# Motor.net
KiCad netlist of a schematic drawn in Altium Designer
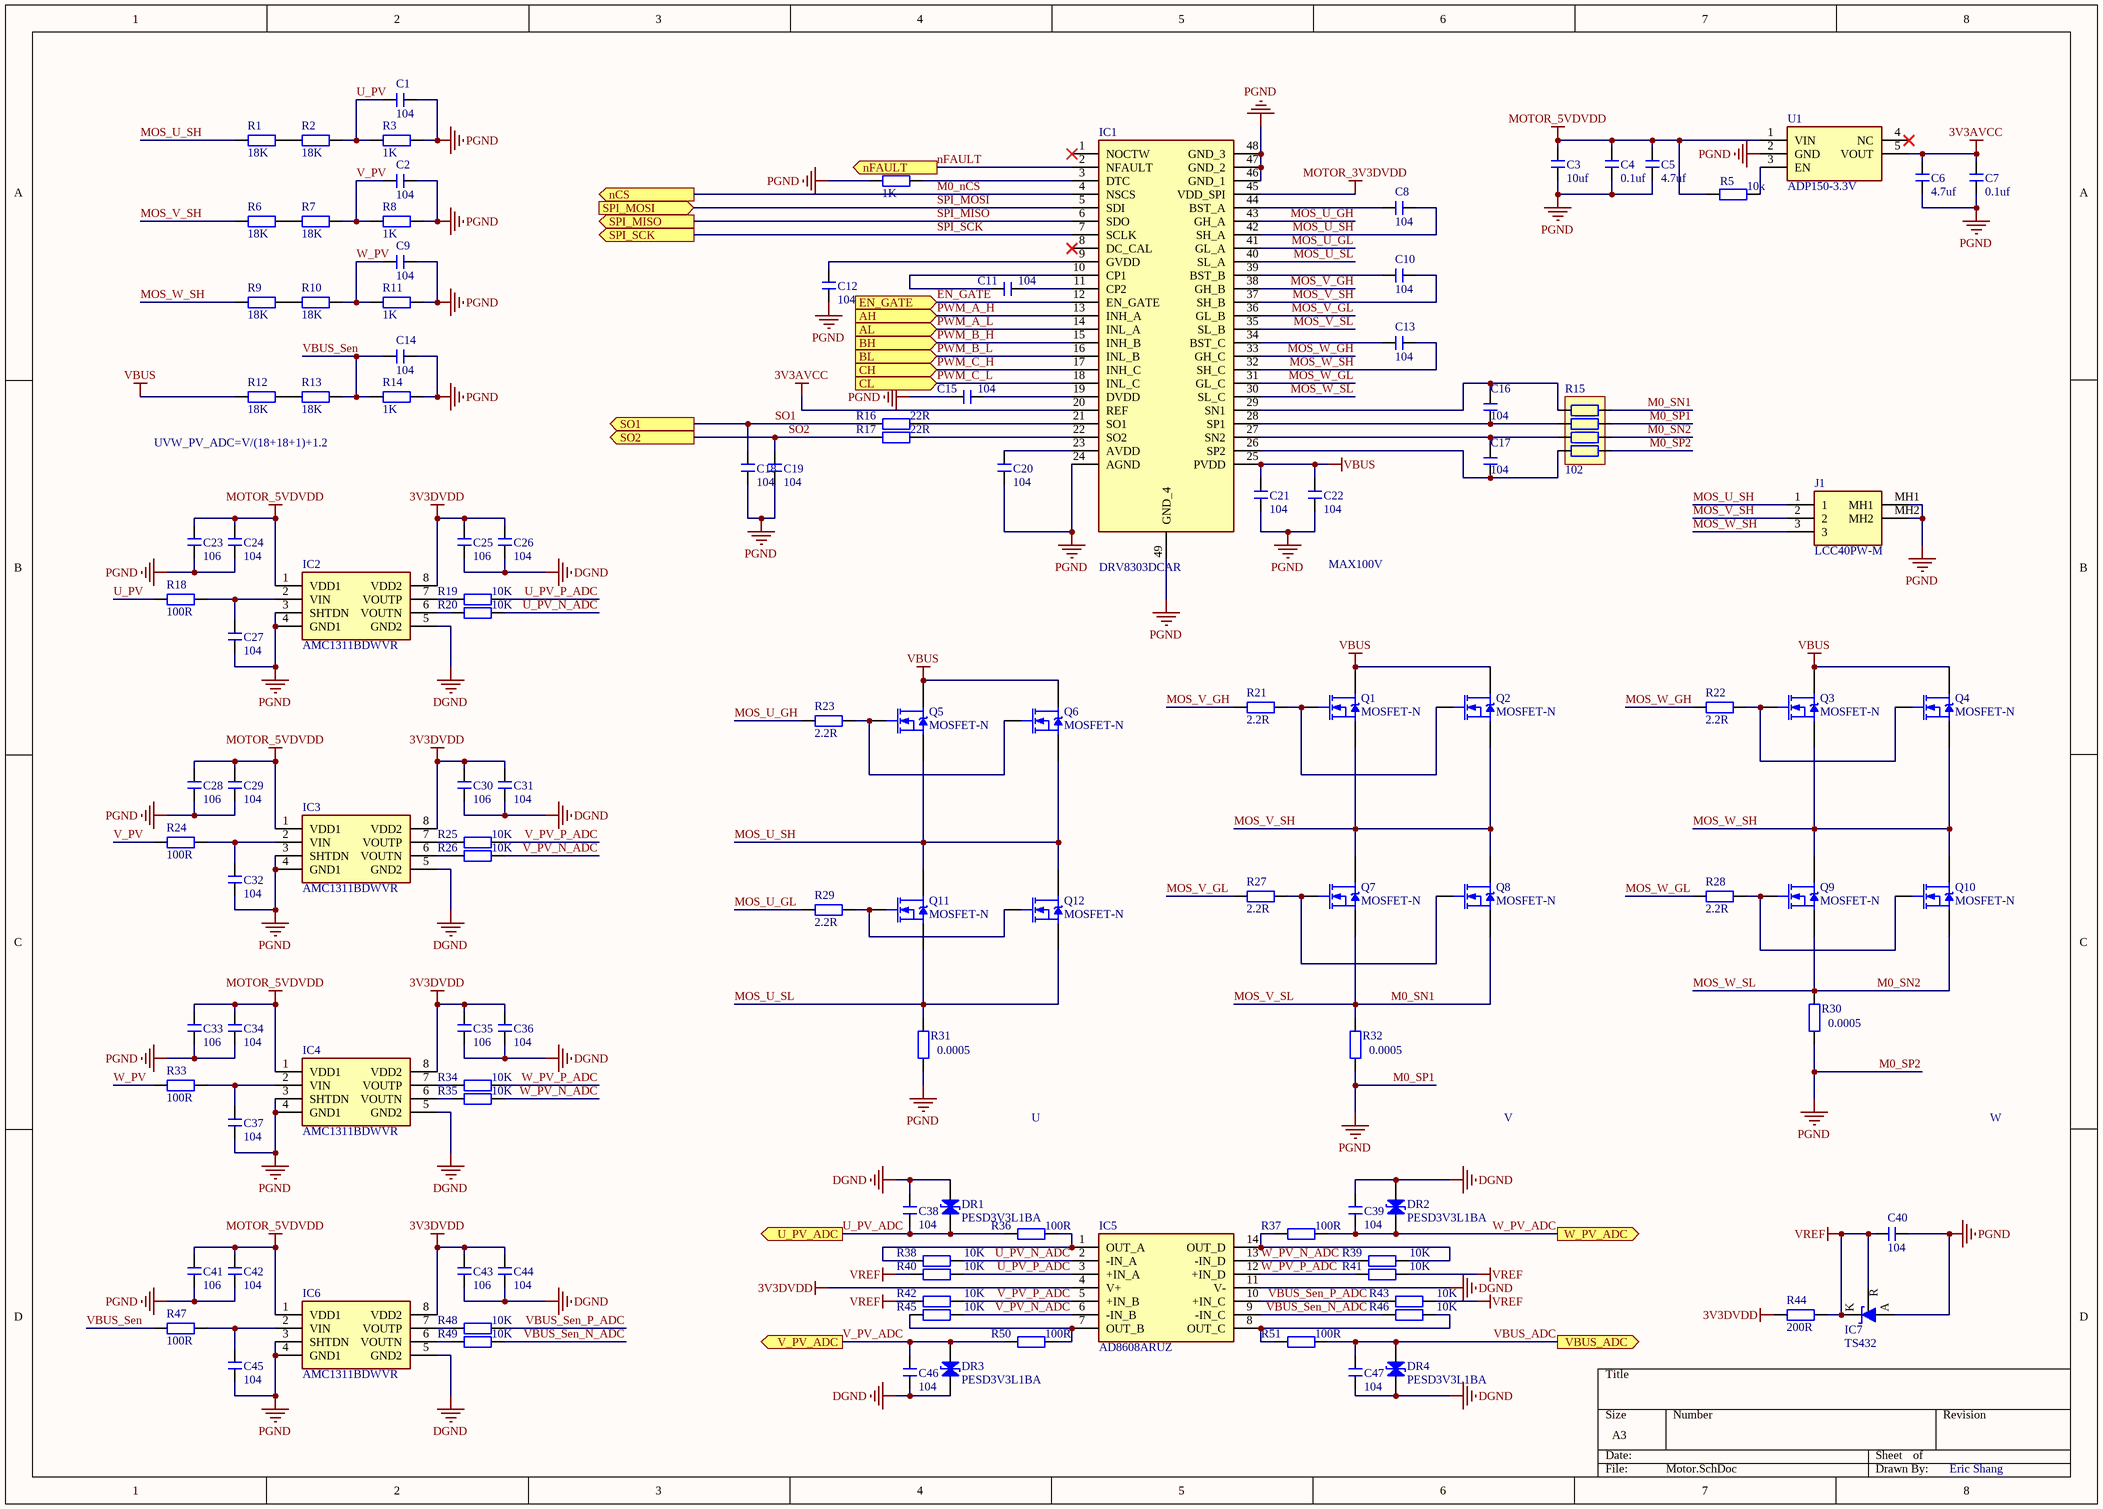
[diagram p0: Motor.SchDoc]

(export (version "E")
  (design (tool "Eeschema 10.0.6"))
  (components
    (comp (ref "C1")
      (value "104")
      (footprint "C 0603_L")
      (description "贴片电容")
      (libsource (lib "0.1 - 电阻-电容-电感") (part "C"))
    )
    (comp (ref "C2")
      (value "104")
      (footprint "C 0603_L")
      (description "贴片电容")
      (libsource (lib "0.1 - 电阻-电容-电感") (part "C"))
    )
    (comp (ref "C3")
      (value "10uf")
      (footprint "C 0805_L")
      (description "贴片电容")
      (libsource (lib "0.1 - 电阻-电容-电感") (part "C"))
    )
    (comp (ref "C4")
      (value "0.1uf")
      (footprint "C 0805_L")
      (description "贴片电容")
      (libsource (lib "0.1 - 电阻-电容-电感") (part "C"))
    )
    (comp (ref "C5")
      (value "4.7uf")
      (footprint "C 0805_L")
      (description "贴片电容")
      (libsource (lib "0.1 - 电阻-电容-电感") (part "C"))
    )
    (comp (ref "C6")
      (value "4.7uf")
      (footprint "C 0805_L")
      (description "贴片电容")
      (libsource (lib "0.1 - 电阻-电容-电感") (part "C"))
    )
    (comp (ref "C7")
      (value "0.1uf")
      (footprint "C 0805_L")
      (description "贴片电容")
      (libsource (lib "0.1 - 电阻-电容-电感") (part "C"))
    )
    (comp (ref "C8")
      (value "104")
      (footprint "C 0603_L")
      (description "贴片电容")
      (libsource (lib "0.1 - 电阻-电容-电感") (part "C"))
    )
    (comp (ref "C9")
      (value "104")
      (footprint "C 0603_L")
      (description "贴片电容")
      (libsource (lib "0.1 - 电阻-电容-电感") (part "C"))
    )
    (comp (ref "C10")
      (value "104")
      (footprint "C 0603_L")
      (description "贴片电容")
      (libsource (lib "0.1 - 电阻-电容-电感") (part "C"))
    )
    (comp (ref "C11")
      (value "104")
      (footprint "C 0603_L")
      (description "贴片电容")
      (libsource (lib "0.1 - 电阻-电容-电感") (part "C"))
    )
    (comp (ref "C12")
      (value "104")
      (footprint "C 0603_L")
      (description "贴片电容")
      (libsource (lib "0.1 - 电阻-电容-电感") (part "C"))
    )
    (comp (ref "C13")
      (value "104")
      (footprint "C 0603_L")
      (description "贴片电容")
      (libsource (lib "0.1 - 电阻-电容-电感") (part "C"))
    )
    (comp (ref "C14")
      (value "104")
      (footprint "C 0603_L")
      (description "贴片电容")
      (libsource (lib "0.1 - 电阻-电容-电感") (part "C"))
    )
    (comp (ref "C15")
      (value "104")
      (footprint "C 0603_L")
      (description "贴片电容")
      (libsource (lib "0.1 - 电阻-电容-电感") (part "C"))
    )
    (comp (ref "C16")
      (value "104")
      (footprint "C 0603_L")
      (description "贴片电容")
      (libsource (lib "0.1 - 电阻-电容-电感") (part "C"))
    )
    (comp (ref "C17")
      (value "104")
      (footprint "C 0603_L")
      (description "贴片电容")
      (libsource (lib "0.1 - 电阻-电容-电感") (part "C"))
    )
    (comp (ref "C18")
      (value "104")
      (footprint "C 0603_L")
      (description "贴片电容")
      (libsource (lib "0.1 - 电阻-电容-电感") (part "C"))
    )
    (comp (ref "C19")
      (value "104")
      (footprint "C 0603_L")
      (description "贴片电容")
      (libsource (lib "0.1 - 电阻-电容-电感") (part "C"))
    )
    (comp (ref "C20")
      (value "104")
      (footprint "C 0603_L")
      (description "贴片电容")
      (libsource (lib "0.1 - 电阻-电容-电感") (part "C"))
    )
    (comp (ref "C21")
      (value "104")
      (footprint "C 0603_L")
      (description "贴片电容")
      (libsource (lib "0.1 - 电阻-电容-电感") (part "C"))
    )
    (comp (ref "C22")
      (value "104")
      (footprint "C 0603_L")
      (description "贴片电容")
      (libsource (lib "0.1 - 电阻-电容-电感") (part "C"))
    )
    (comp (ref "C23")
      (value "106")
      (footprint "C 0603_L")
      (description "贴片电容")
      (libsource (lib "0.1 - 电阻-电容-电感") (part "C"))
    )
    (comp (ref "C24")
      (value "104")
      (footprint "C 0603_L")
      (description "贴片电容")
      (libsource (lib "0.1 - 电阻-电容-电感") (part "C"))
    )
    (comp (ref "C25")
      (value "106")
      (footprint "C 0603_L")
      (description "贴片电容")
      (libsource (lib "0.1 - 电阻-电容-电感") (part "C"))
    )
    (comp (ref "C26")
      (value "104")
      (footprint "C 0603_L")
      (description "贴片电容")
      (libsource (lib "0.1 - 电阻-电容-电感") (part "C"))
    )
    (comp (ref "C27")
      (value "104")
      (footprint "C 0603_L")
      (description "贴片电容")
      (libsource (lib "0.1 - 电阻-电容-电感") (part "C"))
    )
    (comp (ref "C28")
      (value "106")
      (footprint "C 0603_L")
      (description "贴片电容")
      (libsource (lib "0.1 - 电阻-电容-电感") (part "C"))
    )
    (comp (ref "C29")
      (value "104")
      (footprint "C 0603_L")
      (description "贴片电容")
      (libsource (lib "0.1 - 电阻-电容-电感") (part "C"))
    )
    (comp (ref "C30")
      (value "106")
      (footprint "C 0603_L")
      (description "贴片电容")
      (libsource (lib "0.1 - 电阻-电容-电感") (part "C"))
    )
    (comp (ref "C31")
      (value "104")
      (footprint "C 0603_L")
      (description "贴片电容")
      (libsource (lib "0.1 - 电阻-电容-电感") (part "C"))
    )
    (comp (ref "C32")
      (value "104")
      (footprint "C 0603_L")
      (description "贴片电容")
      (libsource (lib "0.1 - 电阻-电容-电感") (part "C"))
    )
    (comp (ref "C33")
      (value "106")
      (footprint "C 0603_L")
      (description "贴片电容")
      (libsource (lib "0.1 - 电阻-电容-电感") (part "C"))
    )
    (comp (ref "C34")
      (value "104")
      (footprint "C 0603_L")
      (description "贴片电容")
      (libsource (lib "0.1 - 电阻-电容-电感") (part "C"))
    )
    (comp (ref "C35")
      (value "106")
      (footprint "C 0603_L")
      (description "贴片电容")
      (libsource (lib "0.1 - 电阻-电容-电感") (part "C"))
    )
    (comp (ref "C36")
      (value "104")
      (footprint "C 0603_L")
      (description "贴片电容")
      (libsource (lib "0.1 - 电阻-电容-电感") (part "C"))
    )
    (comp (ref "C37")
      (value "104")
      (footprint "C 0603_L")
      (description "贴片电容")
      (libsource (lib "0.1 - 电阻-电容-电感") (part "C"))
    )
    (comp (ref "C38")
      (value "104")
      (footprint "C 0603_L")
      (description "贴片电容")
      (libsource (lib "0.1 - 电阻-电容-电感") (part "C"))
    )
    (comp (ref "C39")
      (value "104")
      (footprint "C 0603_L")
      (description "贴片电容")
      (libsource (lib "0.1 - 电阻-电容-电感") (part "C"))
    )
    (comp (ref "C40")
      (value "104")
      (footprint "C 0603_L")
      (description "贴片电容")
      (libsource (lib "0.1 - 电阻-电容-电感") (part "C"))
    )
    (comp (ref "C41")
      (value "106")
      (footprint "C 0603_L")
      (description "贴片电容")
      (libsource (lib "0.1 - 电阻-电容-电感") (part "C"))
    )
    (comp (ref "C42")
      (value "104")
      (footprint "C 0603_L")
      (description "贴片电容")
      (libsource (lib "0.1 - 电阻-电容-电感") (part "C"))
    )
    (comp (ref "C43")
      (value "106")
      (footprint "C 0603_L")
      (description "贴片电容")
      (libsource (lib "0.1 - 电阻-电容-电感") (part "C"))
    )
    (comp (ref "C44")
      (value "104")
      (footprint "C 0603_L")
      (description "贴片电容")
      (libsource (lib "0.1 - 电阻-电容-电感") (part "C"))
    )
    (comp (ref "C45")
      (value "104")
      (footprint "C 0603_L")
      (description "贴片电容")
      (libsource (lib "0.1 - 电阻-电容-电感") (part "C"))
    )
    (comp (ref "C46")
      (value "104")
      (footprint "C 0603_L")
      (description "贴片电容")
      (libsource (lib "0.1 - 电阻-电容-电感") (part "C"))
    )
    (comp (ref "C47")
      (value "104")
      (footprint "C 0603_L")
      (description "贴片电容")
      (libsource (lib "0.1 - 电阻-电容-电感") (part "C"))
    )
    (comp (ref "DR1")
      (value "PESD3V3L1BA")
      (footprint "DO-15")
      (description "瞬态电压抑制二极管")
      (fields (field (name "版权归属") "封装库来自淘宝 ID：黄晶宝石"))
      (libsource (lib "0.2 -  二极管-整流桥") (part "DR"))
    )
    (comp (ref "DR2")
      (value "PESD3V3L1BA")
      (footprint "DO-15")
      (description "瞬态电压抑制二极管")
      (fields (field (name "版权归属") "封装库来自淘宝 ID：黄晶宝石"))
      (libsource (lib "0.2 -  二极管-整流桥") (part "DR"))
    )
    (comp (ref "DR3")
      (value "PESD3V3L1BA")
      (footprint "DO-15")
      (description "瞬态电压抑制二极管")
      (fields (field (name "版权归属") "封装库来自淘宝 ID：黄晶宝石"))
      (libsource (lib "0.2 -  二极管-整流桥") (part "DR"))
    )
    (comp (ref "DR4")
      (value "PESD3V3L1BA")
      (footprint "DO-15")
      (description "瞬态电压抑制二极管")
      (fields (field (name "版权归属") "封装库来自淘宝 ID：黄晶宝石"))
      (libsource (lib "0.2 -  二极管-整流桥") (part "DR"))
    )
    (comp (ref "IC1")
      (value "DRV8303DCAR")
      (footprint "SkylakeADPcbLib:SOP50P810X120-49N")
      (description "Integrated Circuit")
      (fields (field (name "MOUSER PART NUMBER") "595-DRV8303DCAR"))
      (libsource (lib "*") (part "DRV8303DCAR"))
    )
    (comp (ref "IC2")
      (value "AMC1311BDWVR")
      (footprint "SkylakeADPcbLib:SOIC127P1150X280-8N")
      (description "Integrated Circuit")
      (fields (field (name "MOUSER PART NUMBER") "595-AMC1311BDWVR"))
      (libsource (lib "*") (part "AMC1311BDWVR"))
    )
    (comp (ref "IC3")
      (value "AMC1311BDWVR")
      (footprint "SkylakeADPcbLib:SOIC127P1150X280-8N")
      (description "Integrated Circuit")
      (fields (field (name "MOUSER PART NUMBER") "595-AMC1311BDWVR"))
      (libsource (lib "*") (part "AMC1311BDWVR"))
    )
    (comp (ref "IC4")
      (value "AMC1311BDWVR")
      (footprint "SkylakeADPcbLib:SOIC127P1150X280-8N")
      (description "Integrated Circuit")
      (fields (field (name "MOUSER PART NUMBER") "595-AMC1311BDWVR"))
      (libsource (lib "*") (part "AMC1311BDWVR"))
    )
    (comp (ref "IC5")
      (value "AD8608ARUZ")
      (footprint "SkylakeADPcbLib:SOP65P640X120-14N")
      (description "Integrated Circuit")
      (fields (field (name "MOUSER PART NUMBER") "584-AD8608ARUZ"))
      (libsource (lib "*") (part "AD8608ARUZ"))
    )
    (comp (ref "IC6")
      (value "AMC1311BDWVR")
      (footprint "SkylakeADPcbLib:SOIC127P1150X280-8N")
      (description "Integrated Circuit")
      (fields (field (name "MOUSER PART NUMBER") "595-AMC1311BDWVR"))
      (libsource (lib "*") (part "AMC1311BDWVR"))
    )
    (comp (ref "IC7")
      (value "TS432")
      (footprint "SOT23-3N")
      (description "可调基准稳压芯片")
      (fields (field (name "版权归属") "封装库来自淘宝 ID：黄晶宝石"))
      (libsource (lib "1.1 - 电源类芯片") (part "TL431_SMD"))
    )
    (comp (ref "J1")
      (value "LCC40PW-M")
      (footprint "SkylakeADPcbLib:LCC40PWM")
      (description "Connector")
      (libsource (lib "*") (part "LCC40PW-M"))
    )
    (comp (ref "Q1")
      (value "MOSFET-N")
      (footprint "TO263-3B")
      (description "N-Channel MOSFET")
      (fields (field (name "PUBLISHER") "Altium Limited"))
      (libsource (lib "0.5 - 场效应管-可控硅") (part "MOSFET-N"))
    )
    (comp (ref "Q2")
      (value "MOSFET-N")
      (footprint "TO263-3B")
      (description "N-Channel MOSFET")
      (fields (field (name "PUBLISHER") "Altium Limited"))
      (libsource (lib "0.5 - 场效应管-可控硅") (part "MOSFET-N"))
    )
    (comp (ref "Q3")
      (value "MOSFET-N")
      (footprint "TO263-3B")
      (description "N-Channel MOSFET")
      (fields (field (name "PUBLISHER") "Altium Limited"))
      (libsource (lib "0.5 - 场效应管-可控硅") (part "MOSFET-N"))
    )
    (comp (ref "Q4")
      (value "MOSFET-N")
      (footprint "TO263-3B")
      (description "N-Channel MOSFET")
      (fields (field (name "PUBLISHER") "Altium Limited"))
      (libsource (lib "0.5 - 场效应管-可控硅") (part "MOSFET-N"))
    )
    (comp (ref "Q5")
      (value "MOSFET-N")
      (footprint "TO263-3B")
      (description "N-Channel MOSFET")
      (fields (field (name "PUBLISHER") "Altium Limited"))
      (libsource (lib "0.5 - 场效应管-可控硅") (part "MOSFET-N"))
    )
    (comp (ref "Q6")
      (value "MOSFET-N")
      (footprint "TO263-3B")
      (description "N-Channel MOSFET")
      (fields (field (name "PUBLISHER") "Altium Limited"))
      (libsource (lib "0.5 - 场效应管-可控硅") (part "MOSFET-N"))
    )
    (comp (ref "Q7")
      (value "MOSFET-N")
      (footprint "TO263-3B")
      (description "N-Channel MOSFET")
      (fields (field (name "PUBLISHER") "Altium Limited"))
      (libsource (lib "0.5 - 场效应管-可控硅") (part "MOSFET-N"))
    )
    (comp (ref "Q8")
      (value "MOSFET-N")
      (footprint "TO263-3B")
      (description "N-Channel MOSFET")
      (fields (field (name "PUBLISHER") "Altium Limited"))
      (libsource (lib "0.5 - 场效应管-可控硅") (part "MOSFET-N"))
    )
    (comp (ref "Q9")
      (value "MOSFET-N")
      (footprint "TO263-3B")
      (description "N-Channel MOSFET")
      (fields (field (name "PUBLISHER") "Altium Limited"))
      (libsource (lib "0.5 - 场效应管-可控硅") (part "MOSFET-N"))
    )
    (comp (ref "Q10")
      (value "MOSFET-N")
      (footprint "TO263-3B")
      (description "N-Channel MOSFET")
      (fields (field (name "PUBLISHER") "Altium Limited"))
      (libsource (lib "0.5 - 场效应管-可控硅") (part "MOSFET-N"))
    )
    (comp (ref "Q11")
      (value "MOSFET-N")
      (footprint "TO263-3B")
      (description "N-Channel MOSFET")
      (fields (field (name "PUBLISHER") "Altium Limited"))
      (libsource (lib "0.5 - 场效应管-可控硅") (part "MOSFET-N"))
    )
    (comp (ref "Q12")
      (value "MOSFET-N")
      (footprint "TO263-3B")
      (description "N-Channel MOSFET")
      (fields (field (name "PUBLISHER") "Altium Limited"))
      (libsource (lib "0.5 - 场效应管-可控硅") (part "MOSFET-N"))
    )
    (comp (ref "R1")
      (value "18K")
      (footprint "R 0603_L")
      (description "贴片电阻")
      (libsource (lib "0.1 - 电阻-电容-电感") (part "R"))
    )
    (comp (ref "R2")
      (value "18K")
      (footprint "R 0603_L")
      (description "贴片电阻")
      (libsource (lib "0.1 - 电阻-电容-电感") (part "R"))
    )
    (comp (ref "R3")
      (value "1K")
      (footprint "R 0603_L")
      (description "贴片电阻")
      (libsource (lib "0.1 - 电阻-电容-电感") (part "R"))
    )
    (comp (ref "R4")
      (value "1K")
      (footprint "R 0603_L")
      (description "贴片电阻")
      (libsource (lib "0.1 - 电阻-电容-电感") (part "R"))
    )
    (comp (ref "R5")
      (value "10k")
      (footprint "0805_R")
      (description "贴片电阻 0805 电阻")
      (libsource (lib "逍遥封装库") (part "0805 电阻"))
    )
    (comp (ref "R6")
      (value "18K")
      (footprint "R 0603_L")
      (description "贴片电阻")
      (libsource (lib "0.1 - 电阻-电容-电感") (part "R"))
    )
    (comp (ref "R7")
      (value "18K")
      (footprint "R 0603_L")
      (description "贴片电阻")
      (libsource (lib "0.1 - 电阻-电容-电感") (part "R"))
    )
    (comp (ref "R8")
      (value "1K")
      (footprint "R 0603_L")
      (description "贴片电阻")
      (libsource (lib "0.1 - 电阻-电容-电感") (part "R"))
    )
    (comp (ref "R9")
      (value "18K")
      (footprint "R 0603_L")
      (description "贴片电阻")
      (libsource (lib "0.1 - 电阻-电容-电感") (part "R"))
    )
    (comp (ref "R10")
      (value "18K")
      (footprint "R 0603_L")
      (description "贴片电阻")
      (libsource (lib "0.1 - 电阻-电容-电感") (part "R"))
    )
    (comp (ref "R11")
      (value "1K")
      (footprint "R 0603_L")
      (description "贴片电阻")
      (libsource (lib "0.1 - 电阻-电容-电感") (part "R"))
    )
    (comp (ref "R12")
      (value "18K")
      (footprint "R 0603_L")
      (description "贴片电阻")
      (libsource (lib "0.1 - 电阻-电容-电感") (part "R"))
    )
    (comp (ref "R13")
      (value "18K")
      (footprint "R 0603_L")
      (description "贴片电阻")
      (libsource (lib "0.1 - 电阻-电容-电感") (part "R"))
    )
    (comp (ref "R14")
      (value "1K")
      (footprint "R 0603_L")
      (description "贴片电阻")
      (libsource (lib "0.1 - 电阻-电容-电感") (part "R"))
    )
    (comp (ref "R15")
      (value "102")
      (footprint "RCA-8P4R-0603")
      (description "贴片排阻")
      (fields (field (name "版权归属") "封装库来自淘宝 ID：黄晶宝石"))
      (libsource (lib "0.1 - 电阻-电容-电感") (part "R-8P4R"))
    )
    (comp (ref "R16")
      (value "22R")
      (footprint "R 0603_L")
      (description "贴片电阻")
      (libsource (lib "0.1 - 电阻-电容-电感") (part "R"))
    )
    (comp (ref "R17")
      (value "22R")
      (footprint "R 0603_L")
      (description "贴片电阻")
      (libsource (lib "0.1 - 电阻-电容-电感") (part "R"))
    )
    (comp (ref "R18")
      (value "100R")
      (footprint "R 0603_L")
      (description "贴片电阻")
      (libsource (lib "0.1 - 电阻-电容-电感") (part "R"))
    )
    (comp (ref "R19")
      (value "10K")
      (footprint "R 0603_L")
      (description "贴片电阻")
      (libsource (lib "0.1 - 电阻-电容-电感") (part "R"))
    )
    (comp (ref "R20")
      (value "10K")
      (footprint "R 0603_L")
      (description "贴片电阻")
      (libsource (lib "0.1 - 电阻-电容-电感") (part "R"))
    )
    (comp (ref "R21")
      (value "2.2R")
      (footprint "R 0603_L")
      (description "贴片电阻")
      (libsource (lib "0.1 - 电阻-电容-电感") (part "R"))
    )
    (comp (ref "R22")
      (value "2.2R")
      (footprint "R 0603_L")
      (description "贴片电阻")
      (libsource (lib "0.1 - 电阻-电容-电感") (part "R"))
    )
    (comp (ref "R23")
      (value "2.2R")
      (footprint "R 0603_L")
      (description "贴片电阻")
      (libsource (lib "0.1 - 电阻-电容-电感") (part "R"))
    )
    (comp (ref "R24")
      (value "100R")
      (footprint "R 0603_L")
      (description "贴片电阻")
      (libsource (lib "0.1 - 电阻-电容-电感") (part "R"))
    )
    (comp (ref "R25")
      (value "10K")
      (footprint "R 0603_L")
      (description "贴片电阻")
      (libsource (lib "0.1 - 电阻-电容-电感") (part "R"))
    )
    (comp (ref "R26")
      (value "10K")
      (footprint "R 0603_L")
      (description "贴片电阻")
      (libsource (lib "0.1 - 电阻-电容-电感") (part "R"))
    )
    (comp (ref "R27")
      (value "2.2R")
      (footprint "R 0603_L")
      (description "贴片电阻")
      (libsource (lib "0.1 - 电阻-电容-电感") (part "R"))
    )
    (comp (ref "R28")
      (value "2.2R")
      (footprint "R 0603_L")
      (description "贴片电阻")
      (libsource (lib "0.1 - 电阻-电容-电感") (part "R"))
    )
    (comp (ref "R29")
      (value "2.2R")
      (footprint "R 0603_L")
      (description "贴片电阻")
      (libsource (lib "0.1 - 电阻-电容-电感") (part "R"))
    )
    (comp (ref "R30")
      (value "0.0005")
      (footprint "R 2512_M")
      (description "贴片电阻")
      (libsource (lib "0.1 - 电阻-电容-电感") (part "R"))
    )
    (comp (ref "R31")
      (value "0.0005")
      (footprint "R 2512_M")
      (description "贴片电阻")
      (libsource (lib "0.1 - 电阻-电容-电感") (part "R"))
    )
    (comp (ref "R32")
      (value "0.0005")
      (footprint "R 2512_M")
      (description "贴片电阻")
      (libsource (lib "0.1 - 电阻-电容-电感") (part "R"))
    )
    (comp (ref "R33")
      (value "100R")
      (footprint "R 0603_L")
      (description "贴片电阻")
      (libsource (lib "0.1 - 电阻-电容-电感") (part "R"))
    )
    (comp (ref "R34")
      (value "10K")
      (footprint "R 0603_L")
      (description "贴片电阻")
      (libsource (lib "0.1 - 电阻-电容-电感") (part "R"))
    )
    (comp (ref "R35")
      (value "10K")
      (footprint "R 0603_L")
      (description "贴片电阻")
      (libsource (lib "0.1 - 电阻-电容-电感") (part "R"))
    )
    (comp (ref "R36")
      (value "100R")
      (footprint "R 0603_L")
      (description "贴片电阻")
      (libsource (lib "0.1 - 电阻-电容-电感") (part "R"))
    )
    (comp (ref "R37")
      (value "100R")
      (footprint "R 0603_L")
      (description "贴片电阻")
      (libsource (lib "0.1 - 电阻-电容-电感") (part "R"))
    )
    (comp (ref "R38")
      (value "10K")
      (footprint "R 0603_L")
      (description "贴片电阻")
      (libsource (lib "0.1 - 电阻-电容-电感") (part "R"))
    )
    (comp (ref "R39")
      (value "10K")
      (footprint "R 0603_L")
      (description "贴片电阻")
      (libsource (lib "0.1 - 电阻-电容-电感") (part "R"))
    )
    (comp (ref "R40")
      (value "10K")
      (footprint "R 0603_L")
      (description "贴片电阻")
      (libsource (lib "0.1 - 电阻-电容-电感") (part "R"))
    )
    (comp (ref "R41")
      (value "10K")
      (footprint "R 0603_L")
      (description "贴片电阻")
      (libsource (lib "0.1 - 电阻-电容-电感") (part "R"))
    )
    (comp (ref "R42")
      (value "10K")
      (footprint "R 0603_L")
      (description "贴片电阻")
      (libsource (lib "0.1 - 电阻-电容-电感") (part "R"))
    )
    (comp (ref "R43")
      (value "10K")
      (footprint "R 0603_L")
      (description "贴片电阻")
      (libsource (lib "0.1 - 电阻-电容-电感") (part "R"))
    )
    (comp (ref "R44")
      (value "200R")
      (footprint "R 0603_L")
      (description "贴片电阻")
      (libsource (lib "0.1 - 电阻-电容-电感") (part "R"))
    )
    (comp (ref "R45")
      (value "10K")
      (footprint "R 0603_L")
      (description "贴片电阻")
      (libsource (lib "0.1 - 电阻-电容-电感") (part "R"))
    )
    (comp (ref "R46")
      (value "10K")
      (footprint "R 0603_L")
      (description "贴片电阻")
      (libsource (lib "0.1 - 电阻-电容-电感") (part "R"))
    )
    (comp (ref "R47")
      (value "100R")
      (footprint "R 0603_L")
      (description "贴片电阻")
      (libsource (lib "0.1 - 电阻-电容-电感") (part "R"))
    )
    (comp (ref "R48")
      (value "10K")
      (footprint "R 0603_L")
      (description "贴片电阻")
      (libsource (lib "0.1 - 电阻-电容-电感") (part "R"))
    )
    (comp (ref "R49")
      (value "10K")
      (footprint "R 0603_L")
      (description "贴片电阻")
      (libsource (lib "0.1 - 电阻-电容-电感") (part "R"))
    )
    (comp (ref "R50")
      (value "100R")
      (footprint "R 0603_L")
      (description "贴片电阻")
      (libsource (lib "0.1 - 电阻-电容-电感") (part "R"))
    )
    (comp (ref "R51")
      (value "100R")
      (footprint "R 0603_L")
      (description "贴片电阻")
      (libsource (lib "0.1 - 电阻-电容-电感") (part "R"))
    )
    (comp (ref "U1")
      (value "ADP150-3.3V")
      (description "IOVDD needs 1.8V")
      (libsource (lib "CN0383") (part "ADP150"))
    )
  )
  (nets
    (net (code "1") (name "/EN_GATE") (class "Default")
      (node (ref "IC1") (pin "12") (pinfunction "EN_GATE_12") (pintype "passive"))
    )
    (net (code "2") (name "/M0_SN1") (class "Default")
      (node (ref "IC1") (pin "35") (pinfunction "SL_B_35") (pintype "passive"))
      (node (ref "Q7") (pin "3") (pinfunction "S_3") (pintype "passive"))
      (node (ref "Q8") (pin "3") (pinfunction "S_3") (pintype "passive"))
      (node (ref "R15") (pin "8") (pinfunction "8_8") (pintype "passive"))
      (node (ref "R32") (pin "2") (pinfunction "2_2") (pintype "passive"))
    )
    (net (code "3") (name "/M0_SN2") (class "Default")
      (node (ref "IC1") (pin "30") (pinfunction "SL_C_30") (pintype "passive"))
      (node (ref "Q10") (pin "3") (pinfunction "S_3") (pintype "passive"))
      (node (ref "Q9") (pin "3") (pinfunction "S_3") (pintype "passive"))
      (node (ref "R15") (pin "6") (pinfunction "6_6") (pintype "passive"))
      (node (ref "R30") (pin "2") (pinfunction "2_2") (pintype "passive"))
    )
    (net (code "4") (name "/M0_nCS") (class "Default")
      (node (ref "IC1") (pin "4") (pinfunction "NSCS_4") (pintype "passive"))
    )
    (net (code "5") (name "/MOS_U_GH") (class "Default")
      (node (ref "IC1") (pin "43") (pinfunction "GH_A_43") (pintype "passive"))
      (node (ref "R23") (pin "1") (pinfunction "1_1") (pintype "passive"))
    )
    (net (code "6") (name "/MOS_U_GL") (class "Default")
      (node (ref "IC1") (pin "41") (pinfunction "GL_A_41") (pintype "passive"))
      (node (ref "R29") (pin "1") (pinfunction "1_1") (pintype "passive"))
    )
    (net (code "7") (name "/MOS_U_SH") (class "Default")
      (node (ref "C8") (pin "2") (pinfunction "2_2") (pintype "passive"))
      (node (ref "IC1") (pin "42") (pinfunction "SH_A_42") (pintype "passive"))
      (node (ref "J1") (pin "1") (pinfunction "1_1") (pintype "passive"))
      (node (ref "Q11") (pin "2") (pinfunction "D_2") (pintype "passive"))
      (node (ref "Q12") (pin "2") (pinfunction "D_2") (pintype "passive"))
      (node (ref "Q5") (pin "3") (pinfunction "S_3") (pintype "passive"))
      (node (ref "Q6") (pin "3") (pinfunction "S_3") (pintype "passive"))
      (node (ref "R1") (pin "1") (pinfunction "1_1") (pintype "passive"))
    )
    (net (code "8") (name "/MOS_U_SL") (class "Default")
      (node (ref "IC1") (pin "40") (pinfunction "SL_A_40") (pintype "passive"))
      (node (ref "Q11") (pin "3") (pinfunction "S_3") (pintype "passive"))
      (node (ref "Q12") (pin "3") (pinfunction "S_3") (pintype "passive"))
      (node (ref "R31") (pin "2") (pinfunction "2_2") (pintype "passive"))
    )
    (net (code "9") (name "/MOS_V_GH") (class "Default")
      (node (ref "IC1") (pin "38") (pinfunction "GH_B_38") (pintype "passive"))
      (node (ref "R21") (pin "1") (pinfunction "1_1") (pintype "passive"))
    )
    (net (code "10") (name "/MOS_V_GL") (class "Default")
      (node (ref "IC1") (pin "36") (pinfunction "GL_B_36") (pintype "passive"))
      (node (ref "R27") (pin "1") (pinfunction "1_1") (pintype "passive"))
    )
    (net (code "11") (name "/MOS_V_SH") (class "Default")
      (node (ref "C10") (pin "2") (pinfunction "2_2") (pintype "passive"))
      (node (ref "IC1") (pin "37") (pinfunction "SH_B_37") (pintype "passive"))
      (node (ref "J1") (pin "2") (pinfunction "2_2") (pintype "passive"))
      (node (ref "Q1") (pin "3") (pinfunction "S_3") (pintype "passive"))
      (node (ref "Q2") (pin "3") (pinfunction "S_3") (pintype "passive"))
      (node (ref "Q7") (pin "2") (pinfunction "D_2") (pintype "passive"))
      (node (ref "Q8") (pin "2") (pinfunction "D_2") (pintype "passive"))
      (node (ref "R6") (pin "1") (pinfunction "1_1") (pintype "passive"))
    )
    (net (code "12") (name "/MOS_W_GH") (class "Default")
      (node (ref "IC1") (pin "33") (pinfunction "GH_C_33") (pintype "passive"))
      (node (ref "R22") (pin "1") (pinfunction "1_1") (pintype "passive"))
    )
    (net (code "13") (name "/MOS_W_GL") (class "Default")
      (node (ref "IC1") (pin "31") (pinfunction "GL_C_31") (pintype "passive"))
      (node (ref "R28") (pin "1") (pinfunction "1_1") (pintype "passive"))
    )
    (net (code "14") (name "/MOS_W_SH") (class "Default")
      (node (ref "C13") (pin "2") (pinfunction "2_2") (pintype "passive"))
      (node (ref "IC1") (pin "32") (pinfunction "SH_C_32") (pintype "passive"))
      (node (ref "J1") (pin "3") (pinfunction "3_3") (pintype "passive"))
      (node (ref "Q10") (pin "2") (pinfunction "D_2") (pintype "passive"))
      (node (ref "Q3") (pin "3") (pinfunction "S_3") (pintype "passive"))
      (node (ref "Q4") (pin "3") (pinfunction "S_3") (pintype "passive"))
      (node (ref "Q9") (pin "2") (pinfunction "D_2") (pintype "passive"))
      (node (ref "R9") (pin "1") (pinfunction "1_1") (pintype "passive"))
    )
    (net (code "15") (name "/PWM_A_H") (class "Default")
      (node (ref "IC1") (pin "13") (pinfunction "INH_A_13") (pintype "passive"))
    )
    (net (code "16") (name "/PWM_A_L") (class "Default")
      (node (ref "IC1") (pin "14") (pinfunction "INL_A_14") (pintype "passive"))
    )
    (net (code "17") (name "/PWM_B_H") (class "Default")
      (node (ref "IC1") (pin "15") (pinfunction "INH_B_15") (pintype "passive"))
    )
    (net (code "18") (name "/PWM_B_L") (class "Default")
      (node (ref "IC1") (pin "16") (pinfunction "INL_B_16") (pintype "passive"))
    )
    (net (code "19") (name "/PWM_C_H") (class "Default")
      (node (ref "IC1") (pin "17") (pinfunction "INH_C_17") (pintype "passive"))
    )
    (net (code "20") (name "/PWM_C_L") (class "Default")
      (node (ref "IC1") (pin "18") (pinfunction "INL_C_18") (pintype "passive"))
    )
    (net (code "21") (name "/SO1") (class "Default")
      (node (ref "C18") (pin "1") (pinfunction "1_1") (pintype "passive"))
      (node (ref "R16") (pin "1") (pinfunction "1_1") (pintype "passive"))
    )
    (net (code "22") (name "/SO2") (class "Default")
      (node (ref "C19") (pin "1") (pinfunction "1_1") (pintype "passive"))
      (node (ref "R17") (pin "1") (pinfunction "1_1") (pintype "passive"))
    )
    (net (code "23") (name "/SPI_MISO") (class "Default")
      (node (ref "IC1") (pin "6") (pinfunction "SDO_6") (pintype "passive"))
    )
    (net (code "24") (name "/SPI_MOSI") (class "Default")
      (node (ref "IC1") (pin "5") (pinfunction "SDI_5") (pintype "passive"))
    )
    (net (code "25") (name "/SPI_SCK") (class "Default")
      (node (ref "IC1") (pin "7") (pinfunction "SCLK_7") (pintype "passive"))
    )
    (net (code "26") (name "/U_PV") (class "Default")
      (node (ref "C1") (pin "1") (pinfunction "1_1") (pintype "passive"))
      (node (ref "R18") (pin "1") (pinfunction "1_1") (pintype "passive"))
      (node (ref "R2") (pin "2") (pinfunction "2_2") (pintype "passive"))
      (node (ref "R3") (pin "1") (pinfunction "1_1") (pintype "passive"))
    )
    (net (code "27") (name "/U_PV_ADC") (class "Default")
      (node (ref "C38") (pin "2") (pinfunction "2_2") (pintype "passive"))
      (node (ref "DR1") (pin "2") (pinfunction "K_2") (pintype "passive"))
      (node (ref "R36") (pin "2") (pinfunction "2_2") (pintype "passive"))
    )
    (net (code "28") (name "/U_PV_N_ADC") (class "Default")
      (node (ref "IC5") (pin "2") (pinfunction "-IN_A_2") (pintype "passive"))
      (node (ref "R20") (pin "1") (pinfunction "1_1") (pintype "passive"))
      (node (ref "R38") (pin "2") (pinfunction "2_2") (pintype "passive"))
    )
    (net (code "29") (name "/U_PV_P_ADC") (class "Default")
      (node (ref "IC5") (pin "3") (pinfunction "+IN_A_3") (pintype "passive"))
      (node (ref "R19") (pin "1") (pinfunction "1_1") (pintype "passive"))
      (node (ref "R40") (pin "1") (pinfunction "1_1") (pintype "passive"))
    )
    (net (code "30") (name "/VBUS_ADC") (class "Default")
      (node (ref "C47") (pin "1") (pinfunction "1_1") (pintype "passive"))
      (node (ref "DR4") (pin "1") (pinfunction "A_1") (pintype "passive"))
      (node (ref "R51") (pin "1") (pinfunction "1_1") (pintype "passive"))
    )
    (net (code "31") (name "/VBUS_Sen") (class "Default")
      (node (ref "C14") (pin "1") (pinfunction "1_1") (pintype "passive"))
      (node (ref "R13") (pin "2") (pinfunction "2_2") (pintype "passive"))
      (node (ref "R14") (pin "1") (pinfunction "1_1") (pintype "passive"))
      (node (ref "R47") (pin "1") (pinfunction "1_1") (pintype "passive"))
    )
    (net (code "32") (name "/VBUS_Sen_N_ADC") (class "Default")
      (node (ref "IC5") (pin "9") (pinfunction "-IN_C_9") (pintype "passive"))
      (node (ref "R46") (pin "2") (pinfunction "2_2") (pintype "passive"))
      (node (ref "R49") (pin "1") (pinfunction "1_1") (pintype "passive"))
    )
    (net (code "33") (name "/VBUS_Sen_P_ADC") (class "Default")
      (node (ref "IC5") (pin "10") (pinfunction "+IN_C_10") (pintype "passive"))
      (node (ref "R43") (pin "1") (pinfunction "1_1") (pintype "passive"))
      (node (ref "R48") (pin "1") (pinfunction "1_1") (pintype "passive"))
    )
    (net (code "34") (name "/V_PV") (class "Default")
      (node (ref "C2") (pin "1") (pinfunction "1_1") (pintype "passive"))
      (node (ref "R24") (pin "1") (pinfunction "1_1") (pintype "passive"))
      (node (ref "R7") (pin "2") (pinfunction "2_2") (pintype "passive"))
      (node (ref "R8") (pin "1") (pinfunction "1_1") (pintype "passive"))
    )
    (net (code "35") (name "/V_PV_ADC") (class "Default")
      (node (ref "C46") (pin "1") (pinfunction "1_1") (pintype "passive"))
      (node (ref "DR3") (pin "1") (pinfunction "A_1") (pintype "passive"))
      (node (ref "R50") (pin "2") (pinfunction "2_2") (pintype "passive"))
    )
    (net (code "36") (name "/V_PV_N_ADC") (class "Default")
      (node (ref "IC5") (pin "6") (pinfunction "-IN_B_6") (pintype "passive"))
      (node (ref "R26") (pin "1") (pinfunction "1_1") (pintype "passive"))
      (node (ref "R45") (pin "1") (pinfunction "1_1") (pintype "passive"))
    )
    (net (code "37") (name "/V_PV_P_ADC") (class "Default")
      (node (ref "IC5") (pin "5") (pinfunction "+IN_B_5") (pintype "passive"))
      (node (ref "R25") (pin "1") (pinfunction "1_1") (pintype "passive"))
      (node (ref "R42") (pin "2") (pinfunction "2_2") (pintype "passive"))
    )
    (net (code "38") (name "/W_PV") (class "Default")
      (node (ref "C9") (pin "1") (pinfunction "1_1") (pintype "passive"))
      (node (ref "R10") (pin "2") (pinfunction "2_2") (pintype "passive"))
      (node (ref "R11") (pin "1") (pinfunction "1_1") (pintype "passive"))
      (node (ref "R33") (pin "1") (pinfunction "1_1") (pintype "passive"))
    )
    (net (code "39") (name "/W_PV_ADC") (class "Default")
      (node (ref "C39") (pin "2") (pinfunction "2_2") (pintype "passive"))
      (node (ref "DR2") (pin "2") (pinfunction "K_2") (pintype "passive"))
      (node (ref "R37") (pin "1") (pinfunction "1_1") (pintype "passive"))
    )
    (net (code "40") (name "/W_PV_N_ADC") (class "Default")
      (node (ref "IC5") (pin "13") (pinfunction "-IN_D_13") (pintype "passive"))
      (node (ref "R35") (pin "1") (pinfunction "1_1") (pintype "passive"))
      (node (ref "R39") (pin "1") (pinfunction "1_1") (pintype "passive"))
    )
    (net (code "41") (name "/W_PV_P_ADC") (class "Default")
      (node (ref "IC5") (pin "12") (pinfunction "+IN_D_12") (pintype "passive"))
      (node (ref "R34") (pin "1") (pinfunction "1_1") (pintype "passive"))
      (node (ref "R41") (pin "2") (pinfunction "2_2") (pintype "passive"))
    )
    (net (code "42") (name "/nFAULT") (class "Default")
      (node (ref "IC1") (pin "2") (pinfunction "NFAULT_2") (pintype "passive"))
    )
    (net (code "43") (name "3V3AVCC") (class "Default")
      (node (ref "C6") (pin "2") (pinfunction "2_2") (pintype "passive"))
      (node (ref "C7") (pin "2") (pinfunction "2_2") (pintype "passive"))
      (node (ref "IC1") (pin "20") (pinfunction "REF_20") (pintype "passive"))
      (node (ref "U1") (pin "5") (pinfunction "VOUT_5") (pintype "passive"))
    )
    (net (code "44") (name "3V3DVDD") (class "Default")
      (node (ref "C25") (pin "2") (pinfunction "2_2") (pintype "passive"))
      (node (ref "C26") (pin "2") (pinfunction "2_2") (pintype "passive"))
      (node (ref "C30") (pin "2") (pinfunction "2_2") (pintype "passive"))
      (node (ref "C31") (pin "2") (pinfunction "2_2") (pintype "passive"))
      (node (ref "C35") (pin "2") (pinfunction "2_2") (pintype "passive"))
      (node (ref "C36") (pin "2") (pinfunction "2_2") (pintype "passive"))
      (node (ref "C43") (pin "2") (pinfunction "2_2") (pintype "passive"))
      (node (ref "C44") (pin "2") (pinfunction "2_2") (pintype "passive"))
      (node (ref "IC2") (pin "8") (pinfunction "VDD2_8") (pintype "passive"))
      (node (ref "IC3") (pin "8") (pinfunction "VDD2_8") (pintype "passive"))
      (node (ref "IC4") (pin "8") (pinfunction "VDD2_8") (pintype "passive"))
      (node (ref "IC5") (pin "4") (pinfunction "V+_4") (pintype "passive"))
      (node (ref "IC6") (pin "8") (pinfunction "VDD2_8") (pintype "passive"))
      (node (ref "R44") (pin "1") (pinfunction "1_1") (pintype "passive"))
    )
    (net (code "45") (name "DGND") (class "Default")
      (node (ref "C25") (pin "1") (pinfunction "1_1") (pintype "passive"))
      (node (ref "C26") (pin "1") (pinfunction "1_1") (pintype "passive"))
      (node (ref "C30") (pin "1") (pinfunction "1_1") (pintype "passive"))
      (node (ref "C31") (pin "1") (pinfunction "1_1") (pintype "passive"))
      (node (ref "C35") (pin "1") (pinfunction "1_1") (pintype "passive"))
      (node (ref "C36") (pin "1") (pinfunction "1_1") (pintype "passive"))
      (node (ref "C38") (pin "1") (pinfunction "1_1") (pintype "passive"))
      (node (ref "C39") (pin "1") (pinfunction "1_1") (pintype "passive"))
      (node (ref "C43") (pin "1") (pinfunction "1_1") (pintype "passive"))
      (node (ref "C44") (pin "1") (pinfunction "1_1") (pintype "passive"))
      (node (ref "C46") (pin "2") (pinfunction "2_2") (pintype "passive"))
      (node (ref "C47") (pin "2") (pinfunction "2_2") (pintype "passive"))
      (node (ref "DR1") (pin "1") (pinfunction "A_1") (pintype "passive"))
      (node (ref "DR2") (pin "1") (pinfunction "A_1") (pintype "passive"))
      (node (ref "DR3") (pin "2") (pinfunction "K_2") (pintype "passive"))
      (node (ref "DR4") (pin "2") (pinfunction "K_2") (pintype "passive"))
      (node (ref "IC2") (pin "5") (pinfunction "GND2_5") (pintype "passive"))
      (node (ref "IC3") (pin "5") (pinfunction "GND2_5") (pintype "passive"))
      (node (ref "IC4") (pin "5") (pinfunction "GND2_5") (pintype "passive"))
      (node (ref "IC5") (pin "11") (pinfunction "V-_11") (pintype "passive"))
      (node (ref "IC6") (pin "5") (pinfunction "GND2_5") (pintype "passive"))
    )
    (net (code "46") (name "MOTOR_3V3DVDD") (class "Default")
      (node (ref "IC1") (pin "45") (pinfunction "VDD_SPI_45") (pintype "passive"))
    )
    (net (code "47") (name "MOTOR_5VDVDD") (class "Default")
      (node (ref "C23") (pin "2") (pinfunction "2_2") (pintype "passive"))
      (node (ref "C24") (pin "2") (pinfunction "2_2") (pintype "passive"))
      (node (ref "C28") (pin "2") (pinfunction "2_2") (pintype "passive"))
      (node (ref "C29") (pin "2") (pinfunction "2_2") (pintype "passive"))
      (node (ref "C3") (pin "2") (pinfunction "2_2") (pintype "passive"))
      (node (ref "C33") (pin "2") (pinfunction "2_2") (pintype "passive"))
      (node (ref "C34") (pin "2") (pinfunction "2_2") (pintype "passive"))
      (node (ref "C4") (pin "2") (pinfunction "2_2") (pintype "passive"))
      (node (ref "C41") (pin "2") (pinfunction "2_2") (pintype "passive"))
      (node (ref "C42") (pin "2") (pinfunction "2_2") (pintype "passive"))
      (node (ref "C5") (pin "2") (pinfunction "2_2") (pintype "passive"))
      (node (ref "IC2") (pin "1") (pinfunction "VDD1_1") (pintype "passive"))
      (node (ref "IC3") (pin "1") (pinfunction "VDD1_1") (pintype "passive"))
      (node (ref "IC4") (pin "1") (pinfunction "VDD1_1") (pintype "passive"))
      (node (ref "IC6") (pin "1") (pinfunction "VDD1_1") (pintype "passive"))
      (node (ref "R5") (pin "1") (pinfunction "1_1") (pintype "passive"))
      (node (ref "U1") (pin "1") (pinfunction "VIN_1") (pintype "passive"))
    )
    (net (code "48") (name "Net-(IC1-AVDD)") (class "Default")
      (node (ref "C20") (pin "1") (pinfunction "1_1") (pintype "passive"))
      (node (ref "IC1") (pin "23") (pinfunction "AVDD_23") (pintype "passive"))
    )
    (net (code "49") (name "Net-(IC1-BST_A)") (class "Default")
      (node (ref "C8") (pin "1") (pinfunction "1_1") (pintype "passive"))
      (node (ref "IC1") (pin "44") (pinfunction "BST_A_44") (pintype "passive"))
    )
    (net (code "50") (name "Net-(IC1-BST_B)") (class "Default")
      (node (ref "C10") (pin "1") (pinfunction "1_1") (pintype "passive"))
      (node (ref "IC1") (pin "39") (pinfunction "BST_B_39") (pintype "passive"))
    )
    (net (code "51") (name "Net-(IC1-BST_C)") (class "Default")
      (node (ref "C13") (pin "1") (pinfunction "1_1") (pintype "passive"))
      (node (ref "IC1") (pin "34") (pinfunction "BST_C_34") (pintype "passive"))
    )
    (net (code "52") (name "Net-(IC1-CP1)") (class "Default")
      (node (ref "C11") (pin "1") (pinfunction "1_1") (pintype "passive"))
      (node (ref "IC1") (pin "10") (pinfunction "CP1_10") (pintype "passive"))
    )
    (net (code "53") (name "Net-(IC1-CP2)") (class "Default")
      (node (ref "C11") (pin "2") (pinfunction "2_2") (pintype "passive"))
      (node (ref "IC1") (pin "11") (pinfunction "CP2_11") (pintype "passive"))
    )
    (net (code "54") (name "Net-(IC1-DTC)") (class "Default")
      (node (ref "IC1") (pin "3") (pinfunction "DTC_3") (pintype "passive"))
      (node (ref "R4") (pin "2") (pinfunction "2_2") (pintype "passive"))
    )
    (net (code "55") (name "Net-(IC1-DVDD)") (class "Default")
      (node (ref "C15") (pin "2") (pinfunction "2_2") (pintype "passive"))
      (node (ref "IC1") (pin "19") (pinfunction "DVDD_19") (pintype "passive"))
    )
    (net (code "56") (name "Net-(IC1-GVDD)") (class "Default")
      (node (ref "C12") (pin "2") (pinfunction "2_2") (pintype "passive"))
      (node (ref "IC1") (pin "9") (pinfunction "GVDD_9") (pintype "passive"))
    )
    (net (code "57") (name "Net-(IC1-SN1)") (class "Default")
      (node (ref "C16") (pin "2") (pinfunction "2_2") (pintype "passive"))
      (node (ref "IC1") (pin "29") (pinfunction "SN1_29") (pintype "passive"))
      (node (ref "R15") (pin "1") (pinfunction "1_1") (pintype "passive"))
    )
    (net (code "58") (name "Net-(IC1-SN2)") (class "Default")
      (node (ref "C17") (pin "2") (pinfunction "2_2") (pintype "passive"))
      (node (ref "IC1") (pin "27") (pinfunction "SN2_27") (pintype "passive"))
      (node (ref "R15") (pin "3") (pinfunction "3_3") (pintype "passive"))
    )
    (net (code "59") (name "Net-(IC1-SO1)") (class "Default")
      (node (ref "IC1") (pin "21") (pinfunction "SO1_21") (pintype "passive"))
      (node (ref "R16") (pin "2") (pinfunction "2_2") (pintype "passive"))
    )
    (net (code "60") (name "Net-(IC1-SO2)") (class "Default")
      (node (ref "IC1") (pin "22") (pinfunction "SO2_22") (pintype "passive"))
      (node (ref "R17") (pin "2") (pinfunction "2_2") (pintype "passive"))
    )
    (net (code "61") (name "Net-(IC1-SP1)") (class "Default")
      (node (ref "C16") (pin "1") (pinfunction "1_1") (pintype "passive"))
      (node (ref "IC1") (pin "28") (pinfunction "SP1_28") (pintype "passive"))
      (node (ref "R15") (pin "2") (pinfunction "2_2") (pintype "passive"))
    )
    (net (code "62") (name "Net-(IC1-SP2)") (class "Default")
      (node (ref "C17") (pin "1") (pinfunction "1_1") (pintype "passive"))
      (node (ref "IC1") (pin "26") (pinfunction "SP2_26") (pintype "passive"))
      (node (ref "R15") (pin "4") (pinfunction "4_4") (pintype "passive"))
    )
    (net (code "63") (name "Net-(IC2-VIN)") (class "Default")
      (node (ref "C27") (pin "2") (pinfunction "2_2") (pintype "passive"))
      (node (ref "IC2") (pin "2") (pinfunction "VIN_2") (pintype "passive"))
      (node (ref "R18") (pin "2") (pinfunction "2_2") (pintype "passive"))
    )
    (net (code "64") (name "Net-(IC2-VOUTN)") (class "Default")
      (node (ref "IC2") (pin "6") (pinfunction "VOUTN_6") (pintype "passive"))
      (node (ref "R20") (pin "2") (pinfunction "2_2") (pintype "passive"))
    )
    (net (code "65") (name "Net-(IC2-VOUTP)") (class "Default")
      (node (ref "IC2") (pin "7") (pinfunction "VOUTP_7") (pintype "passive"))
      (node (ref "R19") (pin "2") (pinfunction "2_2") (pintype "passive"))
    )
    (net (code "66") (name "Net-(IC3-VIN)") (class "Default")
      (node (ref "C32") (pin "2") (pinfunction "2_2") (pintype "passive"))
      (node (ref "IC3") (pin "2") (pinfunction "VIN_2") (pintype "passive"))
      (node (ref "R24") (pin "2") (pinfunction "2_2") (pintype "passive"))
    )
    (net (code "67") (name "Net-(IC3-VOUTN)") (class "Default")
      (node (ref "IC3") (pin "6") (pinfunction "VOUTN_6") (pintype "passive"))
      (node (ref "R26") (pin "2") (pinfunction "2_2") (pintype "passive"))
    )
    (net (code "68") (name "Net-(IC3-VOUTP)") (class "Default")
      (node (ref "IC3") (pin "7") (pinfunction "VOUTP_7") (pintype "passive"))
      (node (ref "R25") (pin "2") (pinfunction "2_2") (pintype "passive"))
    )
    (net (code "69") (name "Net-(IC4-VIN)") (class "Default")
      (node (ref "C37") (pin "2") (pinfunction "2_2") (pintype "passive"))
      (node (ref "IC4") (pin "2") (pinfunction "VIN_2") (pintype "passive"))
      (node (ref "R33") (pin "2") (pinfunction "2_2") (pintype "passive"))
    )
    (net (code "70") (name "Net-(IC4-VOUTN)") (class "Default")
      (node (ref "IC4") (pin "6") (pinfunction "VOUTN_6") (pintype "passive"))
      (node (ref "R35") (pin "2") (pinfunction "2_2") (pintype "passive"))
    )
    (net (code "71") (name "Net-(IC4-VOUTP)") (class "Default")
      (node (ref "IC4") (pin "7") (pinfunction "VOUTP_7") (pintype "passive"))
      (node (ref "R34") (pin "2") (pinfunction "2_2") (pintype "passive"))
    )
    (net (code "72") (name "Net-(IC5-OUT_A)") (class "Default")
      (node (ref "IC5") (pin "1") (pinfunction "OUT_A_1") (pintype "passive"))
      (node (ref "R36") (pin "1") (pinfunction "1_1") (pintype "passive"))
      (node (ref "R38") (pin "1") (pinfunction "1_1") (pintype "passive"))
    )
    (net (code "73") (name "Net-(IC5-OUT_B)") (class "Default")
      (node (ref "IC5") (pin "7") (pinfunction "OUT_B_7") (pintype "passive"))
      (node (ref "R45") (pin "2") (pinfunction "2_2") (pintype "passive"))
      (node (ref "R50") (pin "1") (pinfunction "1_1") (pintype "passive"))
    )
    (net (code "74") (name "Net-(IC5-OUT_C)") (class "Default")
      (node (ref "IC5") (pin "8") (pinfunction "OUT_C_8") (pintype "passive"))
      (node (ref "R46") (pin "1") (pinfunction "1_1") (pintype "passive"))
      (node (ref "R51") (pin "2") (pinfunction "2_2") (pintype "passive"))
    )
    (net (code "75") (name "Net-(IC5-OUT_D)") (class "Default")
      (node (ref "IC5") (pin "14") (pinfunction "OUT_D_14") (pintype "passive"))
      (node (ref "R37") (pin "2") (pinfunction "2_2") (pintype "passive"))
      (node (ref "R39") (pin "2") (pinfunction "2_2") (pintype "passive"))
    )
    (net (code "76") (name "Net-(IC6-VIN)") (class "Default")
      (node (ref "C45") (pin "2") (pinfunction "2_2") (pintype "passive"))
      (node (ref "IC6") (pin "2") (pinfunction "VIN_2") (pintype "passive"))
      (node (ref "R47") (pin "2") (pinfunction "2_2") (pintype "passive"))
    )
    (net (code "77") (name "Net-(IC6-VOUTN)") (class "Default")
      (node (ref "IC6") (pin "6") (pinfunction "VOUTN_6") (pintype "passive"))
      (node (ref "R49") (pin "2") (pinfunction "2_2") (pintype "passive"))
    )
    (net (code "78") (name "Net-(IC6-VOUTP)") (class "Default")
      (node (ref "IC6") (pin "7") (pinfunction "VOUTP_7") (pintype "passive"))
      (node (ref "R48") (pin "2") (pinfunction "2_2") (pintype "passive"))
    )
    (net (code "79") (name "Net-(Q1-G)") (class "Default")
      (node (ref "Q1") (pin "1") (pinfunction "G_1") (pintype "passive"))
      (node (ref "Q2") (pin "1") (pinfunction "G_1") (pintype "passive"))
      (node (ref "R21") (pin "2") (pinfunction "2_2") (pintype "passive"))
    )
    (net (code "80") (name "Net-(Q3-G)") (class "Default")
      (node (ref "Q3") (pin "1") (pinfunction "G_1") (pintype "passive"))
      (node (ref "Q4") (pin "1") (pinfunction "G_1") (pintype "passive"))
      (node (ref "R22") (pin "2") (pinfunction "2_2") (pintype "passive"))
    )
    (net (code "81") (name "Net-(Q5-G)") (class "Default")
      (node (ref "Q5") (pin "1") (pinfunction "G_1") (pintype "passive"))
      (node (ref "Q6") (pin "1") (pinfunction "G_1") (pintype "passive"))
      (node (ref "R23") (pin "2") (pinfunction "2_2") (pintype "passive"))
    )
    (net (code "82") (name "Net-(Q7-G)") (class "Default")
      (node (ref "Q7") (pin "1") (pinfunction "G_1") (pintype "passive"))
      (node (ref "Q8") (pin "1") (pinfunction "G_1") (pintype "passive"))
      (node (ref "R27") (pin "2") (pinfunction "2_2") (pintype "passive"))
    )
    (net (code "83") (name "Net-(Q10-G)") (class "Default")
      (node (ref "Q10") (pin "1") (pinfunction "G_1") (pintype "passive"))
      (node (ref "Q9") (pin "1") (pinfunction "G_1") (pintype "passive"))
      (node (ref "R28") (pin "2") (pinfunction "2_2") (pintype "passive"))
    )
    (net (code "84") (name "Net-(Q11-G)") (class "Default")
      (node (ref "Q11") (pin "1") (pinfunction "G_1") (pintype "passive"))
      (node (ref "Q12") (pin "1") (pinfunction "G_1") (pintype "passive"))
      (node (ref "R29") (pin "2") (pinfunction "2_2") (pintype "passive"))
    )
    (net (code "85") (name "Net-(R1-Pad2)") (class "Default")
      (node (ref "R1") (pin "2") (pinfunction "2_2") (pintype "passive"))
      (node (ref "R2") (pin "1") (pinfunction "1_1") (pintype "passive"))
    )
    (net (code "86") (name "Net-(R6-Pad2)") (class "Default")
      (node (ref "R6") (pin "2") (pinfunction "2_2") (pintype "passive"))
      (node (ref "R7") (pin "1") (pinfunction "1_1") (pintype "passive"))
    )
    (net (code "87") (name "Net-(R10-Pad1)") (class "Default")
      (node (ref "R10") (pin "1") (pinfunction "1_1") (pintype "passive"))
      (node (ref "R9") (pin "2") (pinfunction "2_2") (pintype "passive"))
    )
    (net (code "88") (name "Net-(R12-Pad2)") (class "Default")
      (node (ref "R12") (pin "2") (pinfunction "2_2") (pintype "passive"))
      (node (ref "R13") (pin "1") (pinfunction "1_1") (pintype "passive"))
    )
    (net (code "89") (name "Net-(U1-EN)") (class "Default")
      (node (ref "R5") (pin "2") (pinfunction "2_2") (pintype "passive"))
      (node (ref "U1") (pin "3") (pinfunction "EN_3") (pintype "passive"))
    )
    (net (code "90") (name "PGND") (class "Default")
      (node (ref "C1") (pin "2") (pinfunction "2_2") (pintype "passive"))
      (node (ref "C12") (pin "1") (pinfunction "1_1") (pintype "passive"))
      (node (ref "C14") (pin "2") (pinfunction "2_2") (pintype "passive"))
      (node (ref "C15") (pin "1") (pinfunction "1_1") (pintype "passive"))
      (node (ref "C18") (pin "2") (pinfunction "2_2") (pintype "passive"))
      (node (ref "C19") (pin "2") (pinfunction "2_2") (pintype "passive"))
      (node (ref "C2") (pin "2") (pinfunction "2_2") (pintype "passive"))
      (node (ref "C20") (pin "2") (pinfunction "2_2") (pintype "passive"))
      (node (ref "C21") (pin "2") (pinfunction "2_2") (pintype "passive"))
      (node (ref "C22") (pin "2") (pinfunction "2_2") (pintype "passive"))
      (node (ref "C23") (pin "1") (pinfunction "1_1") (pintype "passive"))
      (node (ref "C24") (pin "1") (pinfunction "1_1") (pintype "passive"))
      (node (ref "C27") (pin "1") (pinfunction "1_1") (pintype "passive"))
      (node (ref "C28") (pin "1") (pinfunction "1_1") (pintype "passive"))
      (node (ref "C29") (pin "1") (pinfunction "1_1") (pintype "passive"))
      (node (ref "C3") (pin "1") (pinfunction "1_1") (pintype "passive"))
      (node (ref "C32") (pin "1") (pinfunction "1_1") (pintype "passive"))
      (node (ref "C33") (pin "1") (pinfunction "1_1") (pintype "passive"))
      (node (ref "C34") (pin "1") (pinfunction "1_1") (pintype "passive"))
      (node (ref "C37") (pin "1") (pinfunction "1_1") (pintype "passive"))
      (node (ref "C4") (pin "1") (pinfunction "1_1") (pintype "passive"))
      (node (ref "C40") (pin "1") (pinfunction "1_1") (pintype "passive"))
      (node (ref "C41") (pin "1") (pinfunction "1_1") (pintype "passive"))
      (node (ref "C42") (pin "1") (pinfunction "1_1") (pintype "passive"))
      (node (ref "C45") (pin "1") (pinfunction "1_1") (pintype "passive"))
      (node (ref "C5") (pin "1") (pinfunction "1_1") (pintype "passive"))
      (node (ref "C6") (pin "1") (pinfunction "1_1") (pintype "passive"))
      (node (ref "C7") (pin "1") (pinfunction "1_1") (pintype "passive"))
      (node (ref "C9") (pin "2") (pinfunction "2_2") (pintype "passive"))
      (node (ref "IC1") (pin "24") (pinfunction "AGND_24") (pintype "passive"))
      (node (ref "IC1") (pin "46") (pinfunction "GND_1_46") (pintype "passive"))
      (node (ref "IC1") (pin "47") (pinfunction "GND_2_47") (pintype "passive"))
      (node (ref "IC1") (pin "48") (pinfunction "GND_3_48") (pintype "passive"))
      (node (ref "IC1") (pin "49") (pinfunction "GND_4_49") (pintype "passive"))
      (node (ref "IC2") (pin "3") (pinfunction "SHTDN_3") (pintype "passive"))
      (node (ref "IC2") (pin "4") (pinfunction "GND1_4") (pintype "passive"))
      (node (ref "IC3") (pin "3") (pinfunction "SHTDN_3") (pintype "passive"))
      (node (ref "IC3") (pin "4") (pinfunction "GND1_4") (pintype "passive"))
      (node (ref "IC4") (pin "3") (pinfunction "SHTDN_3") (pintype "passive"))
      (node (ref "IC4") (pin "4") (pinfunction "GND1_4") (pintype "passive"))
      (node (ref "IC6") (pin "3") (pinfunction "SHTDN_3") (pintype "passive"))
      (node (ref "IC6") (pin "4") (pinfunction "GND1_4") (pintype "passive"))
      (node (ref "IC7") (pin "3") (pinfunction "A_3") (pintype "passive"))
      (node (ref "J1") (pin "MH1") (pinfunction "MH1_MH1") (pintype "passive"))
      (node (ref "J1") (pin "MH2") (pinfunction "MH2_MH2") (pintype "passive"))
      (node (ref "R11") (pin "2") (pinfunction "2_2") (pintype "passive"))
      (node (ref "R14") (pin "2") (pinfunction "2_2") (pintype "passive"))
      (node (ref "R15") (pin "5") (pinfunction "5_5") (pintype "passive"))
      (node (ref "R15") (pin "7") (pinfunction "7_7") (pintype "passive"))
      (node (ref "R3") (pin "2") (pinfunction "2_2") (pintype "passive"))
      (node (ref "R30") (pin "1") (pinfunction "1_1") (pintype "passive"))
      (node (ref "R31") (pin "1") (pinfunction "1_1") (pintype "passive"))
      (node (ref "R32") (pin "1") (pinfunction "1_1") (pintype "passive"))
      (node (ref "R4") (pin "1") (pinfunction "1_1") (pintype "passive"))
      (node (ref "R8") (pin "2") (pinfunction "2_2") (pintype "passive"))
      (node (ref "U1") (pin "2") (pinfunction "GND_2") (pintype "passive"))
    )
    (net (code "91") (name "VBUS") (class "Default")
      (node (ref "C21") (pin "1") (pinfunction "1_1") (pintype "passive"))
      (node (ref "C22") (pin "1") (pinfunction "1_1") (pintype "passive"))
      (node (ref "IC1") (pin "25") (pinfunction "PVDD_25") (pintype "passive"))
      (node (ref "Q1") (pin "2") (pinfunction "D_2") (pintype "passive"))
      (node (ref "Q2") (pin "2") (pinfunction "D_2") (pintype "passive"))
      (node (ref "Q3") (pin "2") (pinfunction "D_2") (pintype "passive"))
      (node (ref "Q4") (pin "2") (pinfunction "D_2") (pintype "passive"))
      (node (ref "Q5") (pin "2") (pinfunction "D_2") (pintype "passive"))
      (node (ref "Q6") (pin "2") (pinfunction "D_2") (pintype "passive"))
      (node (ref "R12") (pin "1") (pinfunction "1_1") (pintype "passive"))
    )
    (net (code "92") (name "VREF") (class "Default")
      (node (ref "C40") (pin "2") (pinfunction "2_2") (pintype "passive"))
      (node (ref "IC7") (pin "1") (pinfunction "R_1") (pintype "passive"))
      (node (ref "IC7") (pin "2") (pinfunction "K_2") (pintype "passive"))
      (node (ref "R40") (pin "2") (pinfunction "2_2") (pintype "passive"))
      (node (ref "R41") (pin "1") (pinfunction "1_1") (pintype "passive"))
      (node (ref "R42") (pin "1") (pinfunction "1_1") (pintype "passive"))
      (node (ref "R43") (pin "2") (pinfunction "2_2") (pintype "passive"))
      (node (ref "R44") (pin "2") (pinfunction "2_2") (pintype "passive"))
    )
    (net (code "93") (name "unconnected-(IC1-DC_CAL-Pad8)") (class "Default")
      (node (ref "IC1") (pin "8") (pinfunction "DC_CAL_8") (pintype "passive+no_connect"))
    )
    (net (code "94") (name "unconnected-(IC1-NOCTW-Pad1)") (class "Default")
      (node (ref "IC1") (pin "1") (pinfunction "NOCTW_1") (pintype "passive+no_connect"))
    )
    (net (code "95") (name "unconnected-(U1-NC-Pad4)") (class "Default")
      (node (ref "U1") (pin "4") (pinfunction "NC_4") (pintype "passive+no_connect"))
    )
  )
)
